# Vibrationdriver_WS2811.net
KiCad netlist of a schematic drawn in EAGLE
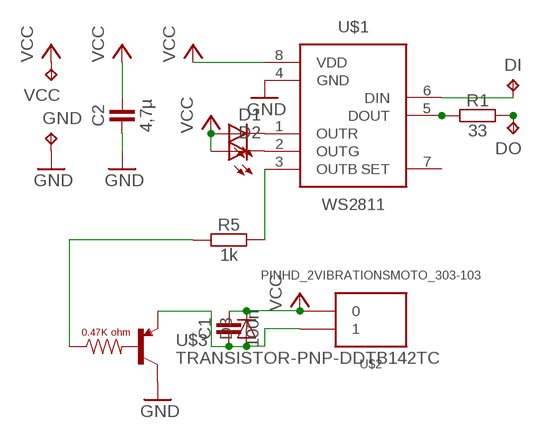
[diagram p0: schematic, sheet 1]

(export (version "E")
  (design (tool "Eeschema 10.0.6"))
  (components
    (comp (ref "C1")
      (value "100n")
      (footprint "eagle-import:C0603")
      (libsource (lib "eagle-import") (part "CAPACITOR-0603"))
    )
    (comp (ref "C2")
      (value "4,7µ")
      (footprint "eagle-import:C0603")
      (libsource (lib "eagle-import") (part "CAPACITOR-0603"))
    )
    (comp (ref "D1")
      (value "LED-0603")
      (footprint "eagle-import:C0603")
      (libsource (lib "eagle-import") (part "LED-0603"))
    )
    (comp (ref "D2")
      (value "LED-0603")
      (footprint "eagle-import:C0603")
      (libsource (lib "eagle-import") (part "LED-0603"))
    )
    (comp (ref "D3")
      (value "DIODE-SOD110")
      (footprint "eagle-import:SOD110")
      (libsource (lib "eagle-import") (part "DIODE-SOD110"))
    )
    (comp (ref "DI")
      (value "TPTP08SQ")
      (footprint "eagle-import:TP08SQ")
      (libsource (lib "eagle-import") (part "TPTP08SQ"))
    )
    (comp (ref "DO")
      (value "TPTP08SQ")
      (footprint "eagle-import:TP08SQ")
      (libsource (lib "eagle-import") (part "TPTP08SQ"))
    )
    (comp (ref "GND")
      (value "TPTP08SQ")
      (footprint "eagle-import:TP08SQ")
      (libsource (lib "eagle-import") (part "TPTP08SQ"))
    )
    (comp (ref "R1")
      (value "33")
      (footprint "eagle-import:C0603")
      (libsource (lib "eagle-import") (part "RESISTOR-0603"))
    )
    (comp (ref "R5")
      (value "1k")
      (footprint "eagle-import:C0603")
      (libsource (lib "eagle-import") (part "RESISTOR-0603"))
    )
    (comp (ref "U$1")
      (value "WS2811")
      (footprint "eagle-import:SOP-8")
      (libsource (lib "eagle-import") (part "WS2811"))
    )
    (comp (ref "U$2")
      (value "PINHD_2VIBRATIONSMOTO_303-103")
      (footprint "eagle-import:VIBRATIONSMOTOR303-103")
      (libsource (lib "eagle-import") (part "PINHD_2VIBRATIONSMOTO_303-103"))
    )
    (comp (ref "U$3")
      (value "TRANSISTOR-PNP-DDTB142TC")
      (footprint "eagle-import:SOT23-3")
      (libsource (lib "eagle-import") (part "TRANSISTOR-PNP-DDTB142TC"))
    )
    (comp (ref "VCC")
      (value "TPTP08SQ")
      (footprint "eagle-import:TP08SQ")
      (libsource (lib "eagle-import") (part "TPTP08SQ"))
    )
  )
  (nets
    (net (code "1") (name "GND") (class "Default")
      (node (ref "C2") (pin "1") (pinfunction "1_1") (pintype "passive"))
      (node (ref "GND") (pin "TP") (pinfunction "TP_TP") (pintype "input"))
      (node (ref "U$1") (pin "4") (pinfunction "GND_4") (pintype "bidirectional"))
      (node (ref "U$3") (pin "3") (pinfunction "C_3") (pintype "passive"))
    )
    (net (code "2") (name "Net-(DO-PadTP)") (class "Default")
      (node (ref "DO") (pin "TP") (pinfunction "TP_TP") (pintype "input"))
      (node (ref "R1") (pin "2") (pinfunction "2_2") (pintype "passive"))
    )
    (net (code "3") (name "Net-(U$1-DIN)") (class "Default")
      (node (ref "DI") (pin "TP") (pinfunction "TP_TP") (pintype "input"))
      (node (ref "U$1") (pin "6") (pinfunction "DIN_6") (pintype "bidirectional"))
    )
    (net (code "4") (name "Net-(U$1-DOUT)") (class "Default")
      (node (ref "R1") (pin "1") (pinfunction "1_1") (pintype "passive"))
      (node (ref "U$1") (pin "5") (pinfunction "DOUT_5") (pintype "bidirectional"))
    )
    (net (code "5") (name "Net-(U$1-OUTB)") (class "Default")
      (node (ref "R5") (pin "2") (pinfunction "2_2") (pintype "passive"))
      (node (ref "U$1") (pin "3") (pinfunction "OUTB_3") (pintype "bidirectional"))
    )
    (net (code "6") (name "Net-(U$1-OUTG)") (class "Default")
      (node (ref "D2") (pin "C") (pinfunction "C_C") (pintype "passive"))
      (node (ref "U$1") (pin "2") (pinfunction "OUTG_2") (pintype "bidirectional"))
    )
    (net (code "7") (name "Net-(U$1-OUTR)") (class "Default")
      (node (ref "D1") (pin "C") (pinfunction "C_C") (pintype "passive"))
      (node (ref "U$1") (pin "1") (pinfunction "OUTR_1") (pintype "bidirectional"))
    )
    (net (code "8") (name "Net-(U$2-1)") (class "Default")
      (node (ref "C1") (pin "1") (pinfunction "1_1") (pintype "passive"))
      (node (ref "D3") (pin "A") (pinfunction "A_A") (pintype "passive"))
      (node (ref "U$2") (pin "2") (pinfunction "1_2") (pintype "bidirectional"))
      (node (ref "U$3") (pin "2") (pinfunction "E_2") (pintype "passive"))
    )
    (net (code "9") (name "Net-(U$3-B)") (class "Default")
      (node (ref "R5") (pin "1") (pinfunction "1_1") (pintype "passive"))
      (node (ref "U$3") (pin "1") (pinfunction "B_1") (pintype "passive"))
    )
    (net (code "10") (name "VCC") (class "Default")
      (node (ref "C1") (pin "2") (pinfunction "2_2") (pintype "passive"))
      (node (ref "C2") (pin "2") (pinfunction "2_2") (pintype "passive"))
      (node (ref "D1") (pin "A") (pinfunction "A_A") (pintype "passive"))
      (node (ref "D2") (pin "A") (pinfunction "A_A") (pintype "passive"))
      (node (ref "D3") (pin "C") (pinfunction "C_C") (pintype "passive"))
      (node (ref "U$1") (pin "8") (pinfunction "VDD_8") (pintype "bidirectional"))
      (node (ref "U$2") (pin "1") (pinfunction "0_1") (pintype "bidirectional"))
      (node (ref "VCC") (pin "TP") (pinfunction "TP_TP") (pintype "input"))
    )
    (net (code "11") (name "unconnected-(U$1-SET-Pad7)") (class "Default")
      (node (ref "U$1") (pin "7") (pinfunction "SET_7") (pintype "bidirectional"))
    )
  )
)
